# 4_-MCU_POWER.net
KiCad netlist of a schematic drawn in Altium Designer
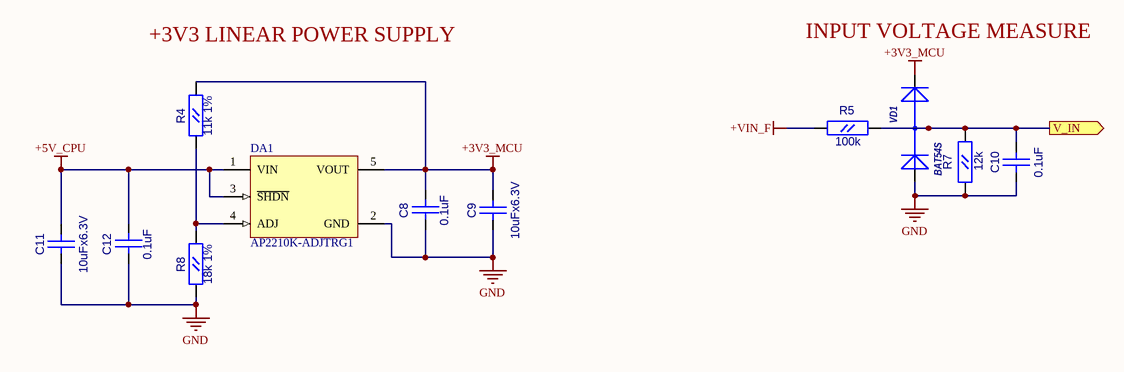
[diagram p0: [4]-MCU_POWER.SchDoc]

(export (version "E")
  (design (tool "Eeschema 10.0.6"))
  (components
    (comp (ref "C8")
      (value "0.1uF")
      (footprint "CC0603")
      (description "CC0603")
      (libsource (lib "gprs_modem_2") (part "CC0603"))
    )
    (comp (ref "C9")
      (value "10uFx6.3V")
      (footprint "CC0805")
      (description "CC0805")
      (libsource (lib "gprs_modem_2") (part "CC0805"))
    )
    (comp (ref "C10")
      (value "0.1uF")
      (footprint "CC0603")
      (description "CC0603")
      (libsource (lib "gprs_modem_2") (part "CC0603"))
    )
    (comp (ref "C11")
      (value "10uFx6.3V")
      (footprint "CC0805")
      (description "CC0805")
      (libsource (lib "gprs_modem_2") (part "CC0805"))
    )
    (comp (ref "C12")
      (value "0.1uF")
      (footprint "CC0603")
      (description "CC0603")
      (libsource (lib "gprs_modem_2") (part "CC0603"))
    )
    (comp (ref "DA1")
      (value "AP2210K-ADJTRG1")
      (footprint "SOT23-5")
      (fields (field (name "PUBLISHER") "Altium Limited"))
      (libsource (lib "gprs_modem_2") (part "MCP1824T-ADJE/OT"))
    )
    (comp (ref "R4")
      (value "11k 1%")
      (footprint "RC0603")
      (description "RC0603")
      (libsource (lib "gprs_modem_2") (part "RC0603"))
    )
    (comp (ref "R5")
      (value "100k")
      (footprint "RC0603")
      (description "RC0603")
      (libsource (lib "gprs_modem_2") (part "RC0603"))
    )
    (comp (ref "R7")
      (value "12k")
      (footprint "RC0603")
      (description "RC0603")
      (libsource (lib "gprs_modem_2") (part "RC0603"))
    )
    (comp (ref "R8")
      (value "18k 1%")
      (footprint "RC0603")
      (description "RC0603")
      (libsource (lib "gprs_modem_2") (part "RC0603"))
    )
    (comp (ref "VD1")
      (value "BAT54S")
      (footprint "SOT-23(GSD)")
      (description "1.0 Ampere General Purpose Rectifier")
      (libsource (lib "gprs_modem_2") (part "BAT54S"))
    )
  )
  (nets
    (net (code "1") (name "+3V3_MCU") (class "Default")
      (node (ref "C8") (pin "1") (pinfunction "A_1") (pintype "passive"))
      (node (ref "C9") (pin "2") (pinfunction "B_2") (pintype "passive"))
      (node (ref "DA1") (pin "5") (pinfunction "VOUT_5") (pintype "power_in"))
      (node (ref "R4") (pin "2") (pinfunction "B_2") (pintype "passive"))
      (node (ref "VD1") (pin "2") (pinfunction "K_2") (pintype "passive"))
    )
    (net (code "2") (name "+5V_CPU") (class "Default")
      (node (ref "C11") (pin "2") (pinfunction "B_2") (pintype "passive"))
      (node (ref "C12") (pin "1") (pinfunction "A_1") (pintype "passive"))
      (node (ref "DA1") (pin "1") (pinfunction "VIN_1") (pintype "power_in"))
      (node (ref "DA1") (pin "3") (pinfunction "~{SHDN}_3") (pintype "input"))
    )
    (net (code "3") (name "+VIN_F") (class "Default")
      (node (ref "R5") (pin "1") (pinfunction "A_1") (pintype "passive"))
    )
    (net (code "4") (name "/V_IN") (class "Default")
      (node (ref "C10") (pin "2") (pinfunction "B_2") (pintype "passive"))
      (node (ref "R5") (pin "2") (pinfunction "B_2") (pintype "passive"))
      (node (ref "R7") (pin "2") (pinfunction "B_2") (pintype "passive"))
      (node (ref "VD1") (pin "3") (pinfunction "AK_3") (pintype "passive"))
    )
    (net (code "5") (name "GND") (class "Default")
      (node (ref "C10") (pin "1") (pinfunction "A_1") (pintype "passive"))
      (node (ref "C11") (pin "1") (pinfunction "A_1") (pintype "passive"))
      (node (ref "C12") (pin "2") (pinfunction "B_2") (pintype "passive"))
      (node (ref "C8") (pin "2") (pinfunction "B_2") (pintype "passive"))
      (node (ref "C9") (pin "1") (pinfunction "A_1") (pintype "passive"))
      (node (ref "DA1") (pin "2") (pinfunction "GND_2") (pintype "power_in"))
      (node (ref "R7") (pin "1") (pinfunction "A_1") (pintype "passive"))
      (node (ref "R8") (pin "1") (pinfunction "A_1") (pintype "passive"))
      (node (ref "VD1") (pin "1") (pinfunction "A_1") (pintype "passive"))
    )
    (net (code "6") (name "Net-(DA1-ADJ)") (class "Default")
      (node (ref "DA1") (pin "4") (pinfunction "ADJ_4") (pintype "input"))
      (node (ref "R4") (pin "1") (pinfunction "A_1") (pintype "passive"))
      (node (ref "R8") (pin "2") (pinfunction "B_2") (pintype "passive"))
    )
  )
)
